# Sheet.net
KiCad netlist of a schematic drawn in Altium Designer
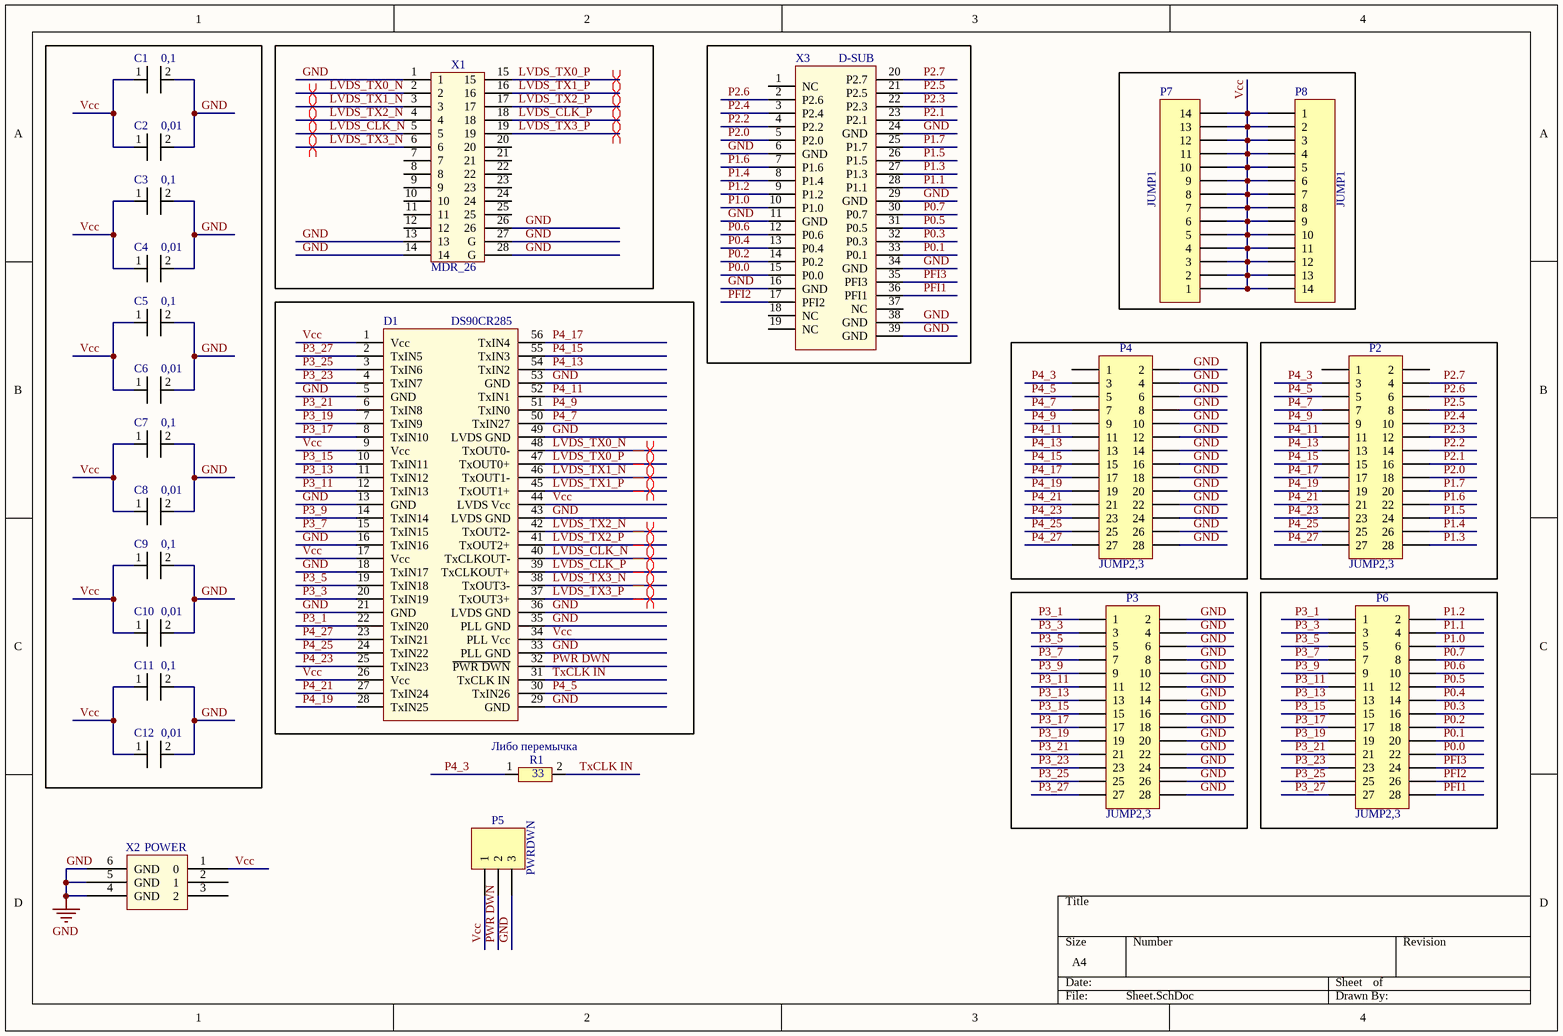
[diagram p0: Sheet.SchDoc]

(export (version "E")
  (design (tool "Eeschema 10.0.6"))
  (components
    (comp (ref "C1") (value "0,1") (footprint "CAP_SMALL") (libsource (lib "Schlib") (part "CAP_SMALL")))
    (comp (ref "C2") (value "0,01") (footprint "CAP_SMALL") (libsource (lib "Schlib") (part "CAP_SMALL")))
    (comp (ref "C3") (value "0,1") (footprint "CAP_SMALL") (libsource (lib "Schlib") (part "CAP_SMALL")))
    (comp (ref "C4") (value "0,01") (footprint "CAP_SMALL") (libsource (lib "Schlib") (part "CAP_SMALL")))
    (comp (ref "C5") (value "0,1") (footprint "CAP_SMALL") (libsource (lib "Schlib") (part "CAP_SMALL")))
    (comp (ref "C6") (value "0,01") (footprint "CAP_SMALL") (libsource (lib "Schlib") (part "CAP_SMALL")))
    (comp (ref "C7") (value "0,1") (footprint "CAP_SMALL") (libsource (lib "Schlib") (part "CAP_SMALL")))
    (comp (ref "C8") (value "0,01") (footprint "CAP_SMALL") (libsource (lib "Schlib") (part "CAP_SMALL")))
    (comp (ref "C9") (value "0,1") (footprint "CAP_SMALL") (libsource (lib "Schlib") (part "CAP_SMALL")))
    (comp (ref "C10") (value "0,01") (footprint "CAP_SMALL") (libsource (lib "Schlib") (part "CAP_SMALL")))
    (comp (ref "C11") (value "0,1") (footprint "CAP_SMALL") (libsource (lib "Schlib") (part "CAP_SMALL")))
    (comp (ref "C12") (value "0,01") (footprint "CAP_SMALL") (libsource (lib "Schlib") (part "CAP_SMALL")))
    (comp (ref "D1") (value "DS90CR285") (footprint "TSSOP56") (libsource (lib "Schlib") (part "DS90CR285")))
    (comp (ref "P2")
      (value "JUMP2,3")
      (footprint "HDR2X14")
      (description "Header, 14-Pin, Dual row")
      (fields (field (name "PUBLISHER") "Altium Limited"))
      (libsource (lib "Miscellaneous Connectors") (part "Header 14X2"))
    )
    (comp (ref "P3")
      (value "JUMP2,3")
      (footprint "HDR2X14")
      (description "Header, 14-Pin, Dual row")
      (fields (field (name "PUBLISHER") "Altium Limited"))
      (libsource (lib "Miscellaneous Connectors") (part "Header 14X2"))
    )
    (comp (ref "P4")
      (value "JUMP2,3")
      (footprint "HDR2X14")
      (description "Header, 14-Pin, Dual row")
      (fields (field (name "PUBLISHER") "Altium Limited"))
      (libsource (lib "Miscellaneous Connectors") (part "Header 14X2"))
    )
    (comp (ref "P5")
      (value "PWRDWN")
      (footprint "HDR1X3")
      (description "Header, 3-Pin")
      (fields (field (name "PUBLISHER") "Altium Limited"))
      (libsource (lib "Miscellaneous Connectors") (part "Header 3"))
    )
    (comp (ref "P6")
      (value "JUMP2,3")
      (footprint "HDR2X14")
      (description "Header, 14-Pin, Dual row")
      (fields (field (name "PUBLISHER") "Altium Limited"))
      (libsource (lib "Miscellaneous Connectors") (part "Header 14X2"))
    )
    (comp (ref "P7")
      (value "JUMP1")
      (footprint "HDR1X14")
      (description "Header, 14-Pin")
      (fields (field (name "PUBLISHER") "Altium Limited"))
      (libsource (lib "") (part "Header 14_1"))
    )
    (comp (ref "P8")
      (value "JUMP1")
      (footprint "HDR1X14")
      (description "Header, 14-Pin")
      (fields (field (name "PUBLISHER") "Altium Limited"))
      (libsource (lib "Miscellaneous Connectors") (part "Header 14"))
    )
    (comp (ref "R1") (value "33") (footprint "RES") (libsource (lib "Schlib") (part "RES")))
    (comp (ref "X1") (value "MDR_26") (footprint "MDR26") (libsource (lib "Schlib") (part "MDR_26")))
    (comp (ref "X2") (value "POWER") (footprint "POWER") (libsource (lib "Schlib") (part "POWER")))
    (comp (ref "X3")
      (value "D-SUB")
      (footprint "CHEAP_CONN_FEMALE")
      (libsource (lib "Schlib") (part "CHEAP_CON_37_FEMALE"))
    )
  )
  (nets
    (net (code "1") (name "/LVDS_CLK_N") (class "Default")
      (node (ref "D1") (pin "40") (pinfunction "TxCLKOUT-_40") (pintype "passive"))
      (node (ref "X1") (pin "5") (pinfunction "5_5") (pintype "passive"))
    )
    (net (code "2") (name "/LVDS_CLK_P") (class "Default")
      (node (ref "D1") (pin "39") (pinfunction "TxCLKOUT+_39") (pintype "passive"))
      (node (ref "X1") (pin "18") (pinfunction "18_18") (pintype "passive"))
    )
    (net (code "3") (name "/LVDS_TX0_N") (class "Default")
      (node (ref "D1") (pin "48") (pinfunction "TxOUT0-_48") (pintype "passive"))
      (node (ref "X1") (pin "2") (pinfunction "2_2") (pintype "passive"))
    )
    (net (code "4") (name "/LVDS_TX0_P") (class "Default")
      (node (ref "D1") (pin "47") (pinfunction "TxOUT0+_47") (pintype "passive"))
      (node (ref "X1") (pin "15") (pinfunction "15_15") (pintype "passive"))
    )
    (net (code "5") (name "/LVDS_TX1_N") (class "Default")
      (node (ref "D1") (pin "46") (pinfunction "TxOUT1-_46") (pintype "passive"))
      (node (ref "X1") (pin "3") (pinfunction "3_3") (pintype "passive"))
    )
    (net (code "6") (name "/LVDS_TX1_P") (class "Default")
      (node (ref "D1") (pin "45") (pinfunction "TxOUT1+_45") (pintype "passive"))
      (node (ref "X1") (pin "16") (pinfunction "16_16") (pintype "passive"))
    )
    (net (code "7") (name "/LVDS_TX2_N") (class "Default")
      (node (ref "D1") (pin "42") (pinfunction "TxOUT2-_42") (pintype "passive"))
      (node (ref "X1") (pin "4") (pinfunction "4_4") (pintype "passive"))
    )
    (net (code "8") (name "/LVDS_TX2_P") (class "Default")
      (node (ref "D1") (pin "41") (pinfunction "TxOUT2+_41") (pintype "passive"))
      (node (ref "X1") (pin "17") (pinfunction "17_17") (pintype "passive"))
    )
    (net (code "9") (name "/LVDS_TX3_N") (class "Default")
      (node (ref "D1") (pin "38") (pinfunction "TxOUT3-_38") (pintype "passive"))
      (node (ref "X1") (pin "6") (pinfunction "6_6") (pintype "passive"))
    )
    (net (code "10") (name "/LVDS_TX3_P") (class "Default")
      (node (ref "D1") (pin "37") (pinfunction "TxOUT3+_37") (pintype "passive"))
      (node (ref "X1") (pin "19") (pinfunction "19_19") (pintype "passive"))
    )
    (net (code "11") (name "/P0.0") (class "Default")
      (node (ref "P6") (pin "22") (pinfunction "22_22") (pintype "passive"))
      (node (ref "X3") (pin "15") (pinfunction "P0.0_15") (pintype "passive"))
    )
    (net (code "12") (name "/P0.1") (class "Default")
      (node (ref "P6") (pin "20") (pinfunction "20_20") (pintype "passive"))
      (node (ref "X3") (pin "33") (pinfunction "P0.1_33") (pintype "passive"))
    )
    (net (code "13") (name "/P0.2") (class "Default")
      (node (ref "P6") (pin "18") (pinfunction "18_18") (pintype "passive"))
      (node (ref "X3") (pin "14") (pinfunction "P0.2_14") (pintype "passive"))
    )
    (net (code "14") (name "/P0.3") (class "Default")
      (node (ref "P6") (pin "16") (pinfunction "16_16") (pintype "passive"))
      (node (ref "X3") (pin "32") (pinfunction "P0.3_32") (pintype "passive"))
    )
    (net (code "15") (name "/P0.4") (class "Default")
      (node (ref "P6") (pin "14") (pinfunction "14_14") (pintype "passive"))
      (node (ref "X3") (pin "13") (pinfunction "P0.4_13") (pintype "passive"))
    )
    (net (code "16") (name "/P0.5") (class "Default")
      (node (ref "P6") (pin "12") (pinfunction "12_12") (pintype "passive"))
      (node (ref "X3") (pin "31") (pinfunction "P0.5_31") (pintype "passive"))
    )
    (net (code "17") (name "/P0.6") (class "Default")
      (node (ref "P6") (pin "10") (pinfunction "10_10") (pintype "passive"))
      (node (ref "X3") (pin "12") (pinfunction "P0.6_12") (pintype "passive"))
    )
    (net (code "18") (name "/P0.7") (class "Default")
      (node (ref "P6") (pin "8") (pinfunction "8_8") (pintype "passive"))
      (node (ref "X3") (pin "30") (pinfunction "P0.7_30") (pintype "passive"))
    )
    (net (code "19") (name "/P1.0") (class "Default")
      (node (ref "P6") (pin "6") (pinfunction "6_6") (pintype "passive"))
      (node (ref "X3") (pin "10") (pinfunction "P1.0_10") (pintype "passive"))
    )
    (net (code "20") (name "/P1.1") (class "Default")
      (node (ref "P6") (pin "4") (pinfunction "4_4") (pintype "passive"))
      (node (ref "X3") (pin "28") (pinfunction "P1.1_28") (pintype "passive"))
    )
    (net (code "21") (name "/P1.2") (class "Default")
      (node (ref "P6") (pin "2") (pinfunction "2_2") (pintype "passive"))
      (node (ref "X3") (pin "9") (pinfunction "P1.2_9") (pintype "passive"))
    )
    (net (code "22") (name "/P1.3") (class "Default")
      (node (ref "P2") (pin "28") (pinfunction "28_28") (pintype "passive"))
      (node (ref "X3") (pin "27") (pinfunction "P1.3_27") (pintype "passive"))
    )
    (net (code "23") (name "/P1.4") (class "Default")
      (node (ref "P2") (pin "26") (pinfunction "26_26") (pintype "passive"))
      (node (ref "X3") (pin "8") (pinfunction "P1.4_8") (pintype "passive"))
    )
    (net (code "24") (name "/P1.5") (class "Default")
      (node (ref "P2") (pin "24") (pinfunction "24_24") (pintype "passive"))
      (node (ref "X3") (pin "26") (pinfunction "P1.5_26") (pintype "passive"))
    )
    (net (code "25") (name "/P1.6") (class "Default")
      (node (ref "P2") (pin "22") (pinfunction "22_22") (pintype "passive"))
      (node (ref "X3") (pin "7") (pinfunction "P1.6_7") (pintype "passive"))
    )
    (net (code "26") (name "/P1.7") (class "Default")
      (node (ref "P2") (pin "20") (pinfunction "20_20") (pintype "passive"))
      (node (ref "X3") (pin "25") (pinfunction "P1.7_25") (pintype "passive"))
    )
    (net (code "27") (name "/P2.0") (class "Default")
      (node (ref "P2") (pin "18") (pinfunction "18_18") (pintype "passive"))
      (node (ref "X3") (pin "5") (pinfunction "P2.0_5") (pintype "passive"))
    )
    (net (code "28") (name "/P2.1") (class "Default")
      (node (ref "P2") (pin "16") (pinfunction "16_16") (pintype "passive"))
      (node (ref "X3") (pin "23") (pinfunction "P2.1_23") (pintype "passive"))
    )
    (net (code "29") (name "/P2.2") (class "Default")
      (node (ref "P2") (pin "14") (pinfunction "14_14") (pintype "passive"))
      (node (ref "X3") (pin "4") (pinfunction "P2.2_4") (pintype "passive"))
    )
    (net (code "30") (name "/P2.3") (class "Default")
      (node (ref "P2") (pin "12") (pinfunction "12_12") (pintype "passive"))
      (node (ref "X3") (pin "22") (pinfunction "P2.3_22") (pintype "passive"))
    )
    (net (code "31") (name "/P2.4") (class "Default")
      (node (ref "P2") (pin "10") (pinfunction "10_10") (pintype "passive"))
      (node (ref "X3") (pin "3") (pinfunction "P2.4_3") (pintype "passive"))
    )
    (net (code "32") (name "/P2.5") (class "Default")
      (node (ref "P2") (pin "8") (pinfunction "8_8") (pintype "passive"))
      (node (ref "X3") (pin "21") (pinfunction "P2.5_21") (pintype "passive"))
    )
    (net (code "33") (name "/P2.6") (class "Default")
      (node (ref "P2") (pin "6") (pinfunction "6_6") (pintype "passive"))
      (node (ref "X3") (pin "2") (pinfunction "P2.6_2") (pintype "passive"))
    )
    (net (code "34") (name "/P2.7") (class "Default")
      (node (ref "P2") (pin "4") (pinfunction "4_4") (pintype "passive"))
      (node (ref "X3") (pin "20") (pinfunction "P2.7_20") (pintype "passive"))
    )
    (net (code "35") (name "/P3_1") (class "Default")
      (node (ref "D1") (pin "22") (pinfunction "TxIN20_22") (pintype "passive"))
      (node (ref "P3") (pin "1") (pinfunction "1_1") (pintype "passive"))
      (node (ref "P6") (pin "1") (pinfunction "1_1") (pintype "passive"))
    )
    (net (code "36") (name "/P3_3") (class "Default")
      (node (ref "D1") (pin "20") (pinfunction "TxIN19_20") (pintype "passive"))
      (node (ref "P3") (pin "3") (pinfunction "3_3") (pintype "passive"))
      (node (ref "P6") (pin "3") (pinfunction "3_3") (pintype "passive"))
    )
    (net (code "37") (name "/P3_5") (class "Default")
      (node (ref "D1") (pin "19") (pinfunction "TxIN18_19") (pintype "passive"))
      (node (ref "P3") (pin "5") (pinfunction "5_5") (pintype "passive"))
      (node (ref "P6") (pin "5") (pinfunction "5_5") (pintype "passive"))
    )
    (net (code "38") (name "/P3_7") (class "Default")
      (node (ref "D1") (pin "15") (pinfunction "TxIN15_15") (pintype "passive"))
      (node (ref "P3") (pin "7") (pinfunction "7_7") (pintype "passive"))
      (node (ref "P6") (pin "7") (pinfunction "7_7") (pintype "passive"))
    )
    (net (code "39") (name "/P3_9") (class "Default")
      (node (ref "D1") (pin "14") (pinfunction "TxIN14_14") (pintype "passive"))
      (node (ref "P3") (pin "9") (pinfunction "9_9") (pintype "passive"))
      (node (ref "P6") (pin "9") (pinfunction "9_9") (pintype "passive"))
    )
    (net (code "40") (name "/P3_11") (class "Default")
      (node (ref "D1") (pin "12") (pinfunction "TxIN13_12") (pintype "passive"))
      (node (ref "P3") (pin "11") (pinfunction "11_11") (pintype "passive"))
      (node (ref "P6") (pin "11") (pinfunction "11_11") (pintype "passive"))
    )
    (net (code "41") (name "/P3_13") (class "Default")
      (node (ref "D1") (pin "11") (pinfunction "TxIN12_11") (pintype "passive"))
      (node (ref "P3") (pin "13") (pinfunction "13_13") (pintype "passive"))
      (node (ref "P6") (pin "13") (pinfunction "13_13") (pintype "passive"))
    )
    (net (code "42") (name "/P3_15") (class "Default")
      (node (ref "D1") (pin "10") (pinfunction "TxIN11_10") (pintype "passive"))
      (node (ref "P3") (pin "15") (pinfunction "15_15") (pintype "passive"))
      (node (ref "P6") (pin "15") (pinfunction "15_15") (pintype "passive"))
    )
    (net (code "43") (name "/P3_17") (class "Default")
      (node (ref "D1") (pin "8") (pinfunction "TxIN10_8") (pintype "passive"))
      (node (ref "P3") (pin "17") (pinfunction "17_17") (pintype "passive"))
      (node (ref "P6") (pin "17") (pinfunction "17_17") (pintype "passive"))
    )
    (net (code "44") (name "/P3_19") (class "Default")
      (node (ref "D1") (pin "7") (pinfunction "TxIN9_7") (pintype "passive"))
      (node (ref "P3") (pin "19") (pinfunction "19_19") (pintype "passive"))
      (node (ref "P6") (pin "19") (pinfunction "19_19") (pintype "passive"))
    )
    (net (code "45") (name "/P3_21") (class "Default")
      (node (ref "D1") (pin "6") (pinfunction "TxIN8_6") (pintype "passive"))
      (node (ref "P3") (pin "21") (pinfunction "21_21") (pintype "passive"))
      (node (ref "P6") (pin "21") (pinfunction "21_21") (pintype "passive"))
    )
    (net (code "46") (name "/P3_23") (class "Default")
      (node (ref "D1") (pin "4") (pinfunction "TxIN7_4") (pintype "passive"))
      (node (ref "P3") (pin "23") (pinfunction "23_23") (pintype "passive"))
      (node (ref "P6") (pin "23") (pinfunction "23_23") (pintype "passive"))
    )
    (net (code "47") (name "/P3_25") (class "Default")
      (node (ref "D1") (pin "3") (pinfunction "TxIN6_3") (pintype "passive"))
      (node (ref "P3") (pin "25") (pinfunction "25_25") (pintype "passive"))
      (node (ref "P6") (pin "25") (pinfunction "25_25") (pintype "passive"))
    )
    (net (code "48") (name "/P3_27") (class "Default")
      (node (ref "D1") (pin "2") (pinfunction "TxIN5_2") (pintype "passive"))
      (node (ref "P3") (pin "27") (pinfunction "27_27") (pintype "passive"))
      (node (ref "P6") (pin "27") (pinfunction "27_27") (pintype "passive"))
    )
    (net (code "49") (name "/P4_3") (class "Default")
      (node (ref "P2") (pin "3") (pinfunction "3_3") (pintype "passive"))
      (node (ref "P4") (pin "3") (pinfunction "3_3") (pintype "passive"))
      (node (ref "R1") (pin "1") (pinfunction "1_1") (pintype "passive"))
    )
    (net (code "50") (name "/P4_5") (class "Default")
      (node (ref "D1") (pin "30") (pinfunction "TxIN26_30") (pintype "passive"))
      (node (ref "P2") (pin "5") (pinfunction "5_5") (pintype "passive"))
      (node (ref "P4") (pin "5") (pinfunction "5_5") (pintype "passive"))
    )
    (net (code "51") (name "/P4_7") (class "Default")
      (node (ref "D1") (pin "50") (pinfunction "TxIN27_50") (pintype "passive"))
      (node (ref "P2") (pin "7") (pinfunction "7_7") (pintype "passive"))
      (node (ref "P4") (pin "7") (pinfunction "7_7") (pintype "passive"))
    )
    (net (code "52") (name "/P4_9") (class "Default")
      (node (ref "D1") (pin "51") (pinfunction "TxIN0_51") (pintype "passive"))
      (node (ref "P2") (pin "9") (pinfunction "9_9") (pintype "passive"))
      (node (ref "P4") (pin "9") (pinfunction "9_9") (pintype "passive"))
    )
    (net (code "53") (name "/P4_11") (class "Default")
      (node (ref "D1") (pin "52") (pinfunction "TxIN1_52") (pintype "passive"))
      (node (ref "P2") (pin "11") (pinfunction "11_11") (pintype "passive"))
      (node (ref "P4") (pin "11") (pinfunction "11_11") (pintype "passive"))
    )
    (net (code "54") (name "/P4_13") (class "Default")
      (node (ref "D1") (pin "54") (pinfunction "TxIN2_54") (pintype "passive"))
      (node (ref "P2") (pin "13") (pinfunction "13_13") (pintype "passive"))
      (node (ref "P4") (pin "13") (pinfunction "13_13") (pintype "passive"))
    )
    (net (code "55") (name "/P4_15") (class "Default")
      (node (ref "D1") (pin "55") (pinfunction "TxIN3_55") (pintype "passive"))
      (node (ref "P2") (pin "15") (pinfunction "15_15") (pintype "passive"))
      (node (ref "P4") (pin "15") (pinfunction "15_15") (pintype "passive"))
    )
    (net (code "56") (name "/P4_17") (class "Default")
      (node (ref "D1") (pin "56") (pinfunction "TxIN4_56") (pintype "passive"))
      (node (ref "P2") (pin "17") (pinfunction "17_17") (pintype "passive"))
      (node (ref "P4") (pin "17") (pinfunction "17_17") (pintype "passive"))
    )
    (net (code "57") (name "/P4_19") (class "Default")
      (node (ref "D1") (pin "28") (pinfunction "TxIN25_28") (pintype "passive"))
      (node (ref "P2") (pin "19") (pinfunction "19_19") (pintype "passive"))
      (node (ref "P4") (pin "19") (pinfunction "19_19") (pintype "passive"))
    )
    (net (code "58") (name "/P4_21") (class "Default")
      (node (ref "D1") (pin "27") (pinfunction "TxIN24_27") (pintype "passive"))
      (node (ref "P2") (pin "21") (pinfunction "21_21") (pintype "passive"))
      (node (ref "P4") (pin "21") (pinfunction "21_21") (pintype "passive"))
    )
    (net (code "59") (name "/P4_23") (class "Default")
      (node (ref "D1") (pin "25") (pinfunction "TxIN23_25") (pintype "passive"))
      (node (ref "P2") (pin "23") (pinfunction "23_23") (pintype "passive"))
      (node (ref "P4") (pin "23") (pinfunction "23_23") (pintype "passive"))
    )
    (net (code "60") (name "/P4_25") (class "Default")
      (node (ref "D1") (pin "24") (pinfunction "TxIN22_24") (pintype "passive"))
      (node (ref "P2") (pin "25") (pinfunction "25_25") (pintype "passive"))
      (node (ref "P4") (pin "25") (pinfunction "25_25") (pintype "passive"))
    )
    (net (code "61") (name "/P4_27") (class "Default")
      (node (ref "D1") (pin "23") (pinfunction "TxIN21_23") (pintype "passive"))
      (node (ref "P2") (pin "27") (pinfunction "27_27") (pintype "passive"))
      (node (ref "P4") (pin "27") (pinfunction "27_27") (pintype "passive"))
    )
    (net (code "62") (name "/PFI1") (class "Default")
      (node (ref "P6") (pin "28") (pinfunction "28_28") (pintype "passive"))
      (node (ref "X3") (pin "36") (pinfunction "PFI1_36") (pintype "passive"))
    )
    (net (code "63") (name "/PFI2") (class "Default")
      (node (ref "P6") (pin "26") (pinfunction "26_26") (pintype "passive"))
      (node (ref "X3") (pin "17") (pinfunction "PFI2_17") (pintype "passive"))
    )
    (net (code "64") (name "/PFI3") (class "Default")
      (node (ref "P6") (pin "24") (pinfunction "24_24") (pintype "passive"))
      (node (ref "X3") (pin "35") (pinfunction "PFI3_35") (pintype "passive"))
    )
    (net (code "65") (name "/PWR DWN") (class "Default")
      (node (ref "D1") (pin "32") (pinfunction "~{PWR_DWN}_32") (pintype "passive"))
      (node (ref "P5") (pin "2") (pinfunction "2_2") (pintype "passive"))
    )
    (net (code "66") (name "/TxCLK IN") (class "Default")
      (node (ref "D1") (pin "31") (pinfunction "TxCLK_IN_31") (pintype "passive"))
      (node (ref "R1") (pin "2") (pinfunction "2_2") (pintype "passive"))
    )
    (net (code "67") (name "/Vcc") (class "Default")
      (node (ref "C1") (pin "1") (pinfunction "1_1") (pintype "passive"))
      (node (ref "C10") (pin "1") (pinfunction "1_1") (pintype "passive"))
      (node (ref "C11") (pin "1") (pinfunction "1_1") (pintype "passive"))
      (node (ref "C12") (pin "1") (pinfunction "1_1") (pintype "passive"))
      (node (ref "C2") (pin "1") (pinfunction "1_1") (pintype "passive"))
      (node (ref "C3") (pin "1") (pinfunction "1_1") (pintype "passive"))
      (node (ref "C4") (pin "1") (pinfunction "1_1") (pintype "passive"))
      (node (ref "C5") (pin "1") (pinfunction "1_1") (pintype "passive"))
      (node (ref "C6") (pin "1") (pinfunction "1_1") (pintype "passive"))
      (node (ref "C7") (pin "1") (pinfunction "1_1") (pintype "passive"))
      (node (ref "C8") (pin "1") (pinfunction "1_1") (pintype "passive"))
      (node (ref "C9") (pin "1") (pinfunction "1_1") (pintype "passive"))
      (node (ref "D1") (pin "1") (pinfunction "Vcc_1") (pintype "passive"))
      (node (ref "D1") (pin "17") (pinfunction "Vcc_17") (pintype "passive"))
      (node (ref "D1") (pin "26") (pinfunction "Vcc_26") (pintype "passive"))
      (node (ref "D1") (pin "34") (pinfunction "PLL_Vcc_34") (pintype "passive"))
      (node (ref "D1") (pin "44") (pinfunction "LVDS_Vcc_44") (pintype "passive"))
      (node (ref "D1") (pin "9") (pinfunction "Vcc_9") (pintype "passive"))
      (node (ref "P5") (pin "1") (pinfunction "1_1") (pintype "passive"))
      (node (ref "P7") (pin "1") (pinfunction "1_1") (pintype "passive"))
      (node (ref "P7") (pin "10") (pinfunction "10_10") (pintype "passive"))
      (node (ref "P7") (pin "11") (pinfunction "11_11") (pintype "passive"))
      (node (ref "P7") (pin "12") (pinfunction "12_12") (pintype "passive"))
      (node (ref "P7") (pin "13") (pinfunction "13_13") (pintype "passive"))
      (node (ref "P7") (pin "14") (pinfunction "14_14") (pintype "passive"))
      (node (ref "P7") (pin "2") (pinfunction "2_2") (pintype "passive"))
      (node (ref "P7") (pin "3") (pinfunction "3_3") (pintype "passive"))
      (node (ref "P7") (pin "4") (pinfunction "4_4") (pintype "passive"))
      (node (ref "P7") (pin "5") (pinfunction "5_5") (pintype "passive"))
      (node (ref "P7") (pin "6") (pinfunction "6_6") (pintype "passive"))
      (node (ref "P7") (pin "7") (pinfunction "7_7") (pintype "passive"))
      (node (ref "P7") (pin "8") (pinfunction "8_8") (pintype "passive"))
      (node (ref "P7") (pin "9") (pinfunction "9_9") (pintype "passive"))
      (node (ref "P8") (pin "1") (pinfunction "1_1") (pintype "passive"))
      (node (ref "P8") (pin "10") (pinfunction "10_10") (pintype "passive"))
      (node (ref "P8") (pin "11") (pinfunction "11_11") (pintype "passive"))
      (node (ref "P8") (pin "12") (pinfunction "12_12") (pintype "passive"))
      (node (ref "P8") (pin "13") (pinfunction "13_13") (pintype "passive"))
      (node (ref "P8") (pin "14") (pinfunction "14_14") (pintype "passive"))
      (node (ref "P8") (pin "2") (pinfunction "2_2") (pintype "passive"))
      (node (ref "P8") (pin "3") (pinfunction "3_3") (pintype "passive"))
      (node (ref "P8") (pin "4") (pinfunction "4_4") (pintype "passive"))
      (node (ref "P8") (pin "5") (pinfunction "5_5") (pintype "passive"))
      (node (ref "P8") (pin "6") (pinfunction "6_6") (pintype "passive"))
      (node (ref "P8") (pin "7") (pinfunction "7_7") (pintype "passive"))
      (node (ref "P8") (pin "8") (pinfunction "8_8") (pintype "passive"))
      (node (ref "P8") (pin "9") (pinfunction "9_9") (pintype "passive"))
      (node (ref "X2") (pin "1") (pinfunction "0_1") (pintype "passive"))
    )
    (net (code "68") (name "GND") (class "Default")
      (node (ref "C1") (pin "2") (pinfunction "2_2") (pintype "passive"))
      (node (ref "C10") (pin "2") (pinfunction "2_2") (pintype "passive"))
      (node (ref "C11") (pin "2") (pinfunction "2_2") (pintype "passive"))
      (node (ref "C12") (pin "2") (pinfunction "2_2") (pintype "passive"))
      (node (ref "C2") (pin "2") (pinfunction "2_2") (pintype "passive"))
      (node (ref "C3") (pin "2") (pinfunction "2_2") (pintype "passive"))
      (node (ref "C4") (pin "2") (pinfunction "2_2") (pintype "passive"))
      (node (ref "C5") (pin "2") (pinfunction "2_2") (pintype "passive"))
      (node (ref "C6") (pin "2") (pinfunction "2_2") (pintype "passive"))
      (node (ref "C7") (pin "2") (pinfunction "2_2") (pintype "passive"))
      (node (ref "C8") (pin "2") (pinfunction "2_2") (pintype "passive"))
      (node (ref "C9") (pin "2") (pinfunction "2_2") (pintype "passive"))
      (node (ref "D1") (pin "13") (pinfunction "GND_13") (pintype "passive"))
      (node (ref "D1") (pin "16") (pinfunction "TxIN16_16") (pintype "passive"))
      (node (ref "D1") (pin "18") (pinfunction "TxIN17_18") (pintype "passive"))
      (node (ref "D1") (pin "21") (pinfunction "GND_21") (pintype "passive"))
      (node (ref "D1") (pin "29") (pinfunction "GND_29") (pintype "passive"))
      (node (ref "D1") (pin "33") (pinfunction "PLL_GND_33") (pintype "passive"))
      (node (ref "D1") (pin "35") (pinfunction "PLL_GND_35") (pintype "passive"))
      (node (ref "D1") (pin "36") (pinfunction "LVDS_GND_36") (pintype "passive"))
      (node (ref "D1") (pin "43") (pinfunction "LVDS_GND_43") (pintype "passive"))
      (node (ref "D1") (pin "49") (pinfunction "LVDS_GND_49") (pintype "passive"))
      (node (ref "D1") (pin "5") (pinfunction "GND_5") (pintype "passive"))
      (node (ref "D1") (pin "53") (pinfunction "GND_53") (pintype "passive"))
      (node (ref "P3") (pin "10") (pinfunction "10_10") (pintype "passive"))
      (node (ref "P3") (pin "12") (pinfunction "12_12") (pintype "passive"))
      (node (ref "P3") (pin "14") (pinfunction "14_14") (pintype "passive"))
      (node (ref "P3") (pin "16") (pinfunction "16_16") (pintype "passive"))
      (node (ref "P3") (pin "18") (pinfunction "18_18") (pintype "passive"))
      (node (ref "P3") (pin "2") (pinfunction "2_2") (pintype "passive"))
      (node (ref "P3") (pin "20") (pinfunction "20_20") (pintype "passive"))
      (node (ref "P3") (pin "22") (pinfunction "22_22") (pintype "passive"))
      (node (ref "P3") (pin "24") (pinfunction "24_24") (pintype "passive"))
      (node (ref "P3") (pin "26") (pinfunction "26_26") (pintype "passive"))
      (node (ref "P3") (pin "28") (pinfunction "28_28") (pintype "passive"))
      (node (ref "P3") (pin "4") (pinfunction "4_4") (pintype "passive"))
      (node (ref "P3") (pin "6") (pinfunction "6_6") (pintype "passive"))
      (node (ref "P3") (pin "8") (pinfunction "8_8") (pintype "passive"))
      (node (ref "P4") (pin "10") (pinfunction "10_10") (pintype "passive"))
      (node (ref "P4") (pin "12") (pinfunction "12_12") (pintype "passive"))
      (node (ref "P4") (pin "14") (pinfunction "14_14") (pintype "passive"))
      (node (ref "P4") (pin "16") (pinfunction "16_16") (pintype "passive"))
      (node (ref "P4") (pin "18") (pinfunction "18_18") (pintype "passive"))
      (node (ref "P4") (pin "2") (pinfunction "2_2") (pintype "passive"))
      (node (ref "P4") (pin "20") (pinfunction "20_20") (pintype "passive"))
      (node (ref "P4") (pin "22") (pinfunction "22_22") (pintype "passive"))
      (node (ref "P4") (pin "24") (pinfunction "24_24") (pintype "passive"))
      (node (ref "P4") (pin "26") (pinfunction "26_26") (pintype "passive"))
      (node (ref "P4") (pin "28") (pinfunction "28_28") (pintype "passive"))
      (node (ref "P4") (pin "4") (pinfunction "4_4") (pintype "passive"))
      (node (ref "P4") (pin "6") (pinfunction "6_6") (pintype "passive"))
      (node (ref "P4") (pin "8") (pinfunction "8_8") (pintype "passive"))
      (node (ref "P5") (pin "3") (pinfunction "3_3") (pintype "passive"))
      (node (ref "X1") (pin "1") (pinfunction "1_1") (pintype "passive"))
      (node (ref "X1") (pin "13") (pinfunction "13_13") (pintype "passive"))
      (node (ref "X1") (pin "14") (pinfunction "14_14") (pintype "passive"))
      (node (ref "X1") (pin "26") (pinfunction "26_26") (pintype "passive"))
      (node (ref "X1") (pin "27") (pinfunction "G_27") (pintype "passive"))
      (node (ref "X1") (pin "28") (pinfunction "G_28") (pintype "passive"))
      (node (ref "X2") (pin "4") (pinfunction "GND_4") (pintype "passive"))
      (node (ref "X2") (pin "5") (pinfunction "GND_5") (pintype "passive"))
      (node (ref "X2") (pin "6") (pinfunction "GND_6") (pintype "passive"))
      (node (ref "X3") (pin "11") (pinfunction "GND_11") (pintype "passive"))
      (node (ref "X3") (pin "16") (pinfunction "GND_16") (pintype "passive"))
      (node (ref "X3") (pin "24") (pinfunction "GND_24") (pintype "passive"))
      (node (ref "X3") (pin "29") (pinfunction "GND_29") (pintype "passive"))
      (node (ref "X3") (pin "34") (pinfunction "GND_34") (pintype "passive"))
      (node (ref "X3") (pin "38") (pinfunction "GND_38") (pintype "passive"))
      (node (ref "X3") (pin "39") (pinfunction "GND_39") (pintype "passive"))
      (node (ref "X3") (pin "6") (pinfunction "GND_6") (pintype "passive"))
    )
    (net (code "69") (name "unconnected-(P2-Pad1)") (class "Default")
      (node (ref "P2") (pin "1") (pinfunction "1_1") (pintype "passive"))
    )
    (net (code "70") (name "unconnected-(P2-Pad2)") (class "Default")
      (node (ref "P2") (pin "2") (pinfunction "2_2") (pintype "passive"))
    )
    (net (code "71") (name "unconnected-(P4-Pad1)") (class "Default")
      (node (ref "P4") (pin "1") (pinfunction "1_1") (pintype "passive"))
    )
    (net (code "72") (name "unconnected-(X1-Pad7)") (class "Default")
      (node (ref "X1") (pin "7") (pinfunction "7_7") (pintype "passive"))
    )
    (net (code "73") (name "unconnected-(X1-Pad8)") (class "Default")
      (node (ref "X1") (pin "8") (pinfunction "8_8") (pintype "passive"))
    )
    (net (code "74") (name "unconnected-(X1-Pad9)") (class "Default")
      (node (ref "X1") (pin "9") (pinfunction "9_9") (pintype "passive"))
    )
    (net (code "75") (name "unconnected-(X1-Pad10)") (class "Default")
      (node (ref "X1") (pin "10") (pinfunction "10_10") (pintype "passive"))
    )
    (net (code "76") (name "unconnected-(X1-Pad11)") (class "Default")
      (node (ref "X1") (pin "11") (pinfunction "11_11") (pintype "passive"))
    )
    (net (code "77") (name "unconnected-(X1-Pad12)") (class "Default")
      (node (ref "X1") (pin "12") (pinfunction "12_12") (pintype "passive"))
    )
    (net (code "78") (name "unconnected-(X1-Pad20)") (class "Default")
      (node (ref "X1") (pin "20") (pinfunction "20_20") (pintype "passive"))
    )
    (net (code "79") (name "unconnected-(X1-Pad21)") (class "Default")
      (node (ref "X1") (pin "21") (pinfunction "21_21") (pintype "passive"))
    )
    (net (code "80") (name "unconnected-(X1-Pad22)") (class "Default")
      (node (ref "X1") (pin "22") (pinfunction "22_22") (pintype "passive"))
    )
    (net (code "81") (name "unconnected-(X1-Pad23)") (class "Default")
      (node (ref "X1") (pin "23") (pinfunction "23_23") (pintype "passive"))
    )
    (net (code "82") (name "unconnected-(X1-Pad24)") (class "Default")
      (node (ref "X1") (pin "24") (pinfunction "24_24") (pintype "passive"))
    )
    (net (code "83") (name "unconnected-(X1-Pad25)") (class "Default")
      (node (ref "X1") (pin "25") (pinfunction "25_25") (pintype "passive"))
    )
    (net (code "84") (name "unconnected-(X2-1-Pad2)") (class "Default")
      (node (ref "X2") (pin "2") (pinfunction "1_2") (pintype "passive"))
    )
    (net (code "85") (name "unconnected-(X2-2-Pad3)") (class "Default")
      (node (ref "X2") (pin "3") (pinfunction "2_3") (pintype "passive"))
    )
    (net (code "86") (name "unconnected-(X3-NC-Pad1)") (class "Default")
      (node (ref "X3") (pin "1") (pinfunction "NC_1") (pintype "passive"))
    )
    (net (code "87") (name "unconnected-(X3-NC-Pad18)") (class "Default")
      (node (ref "X3") (pin "18") (pinfunction "NC_18") (pintype "passive"))
    )
    (net (code "88") (name "unconnected-(X3-NC-Pad19)") (class "Default")
      (node (ref "X3") (pin "19") (pinfunction "NC_19") (pintype "passive"))
    )
    (net (code "89") (name "unconnected-(X3-NC-Pad37)") (class "Default")
      (node (ref "X3") (pin "37") (pinfunction "NC_37") (pintype "passive"))
    )
  )
)
